# Air_Quality_Sensors.net
KiCad netlist of a schematic drawn in Altium Designer
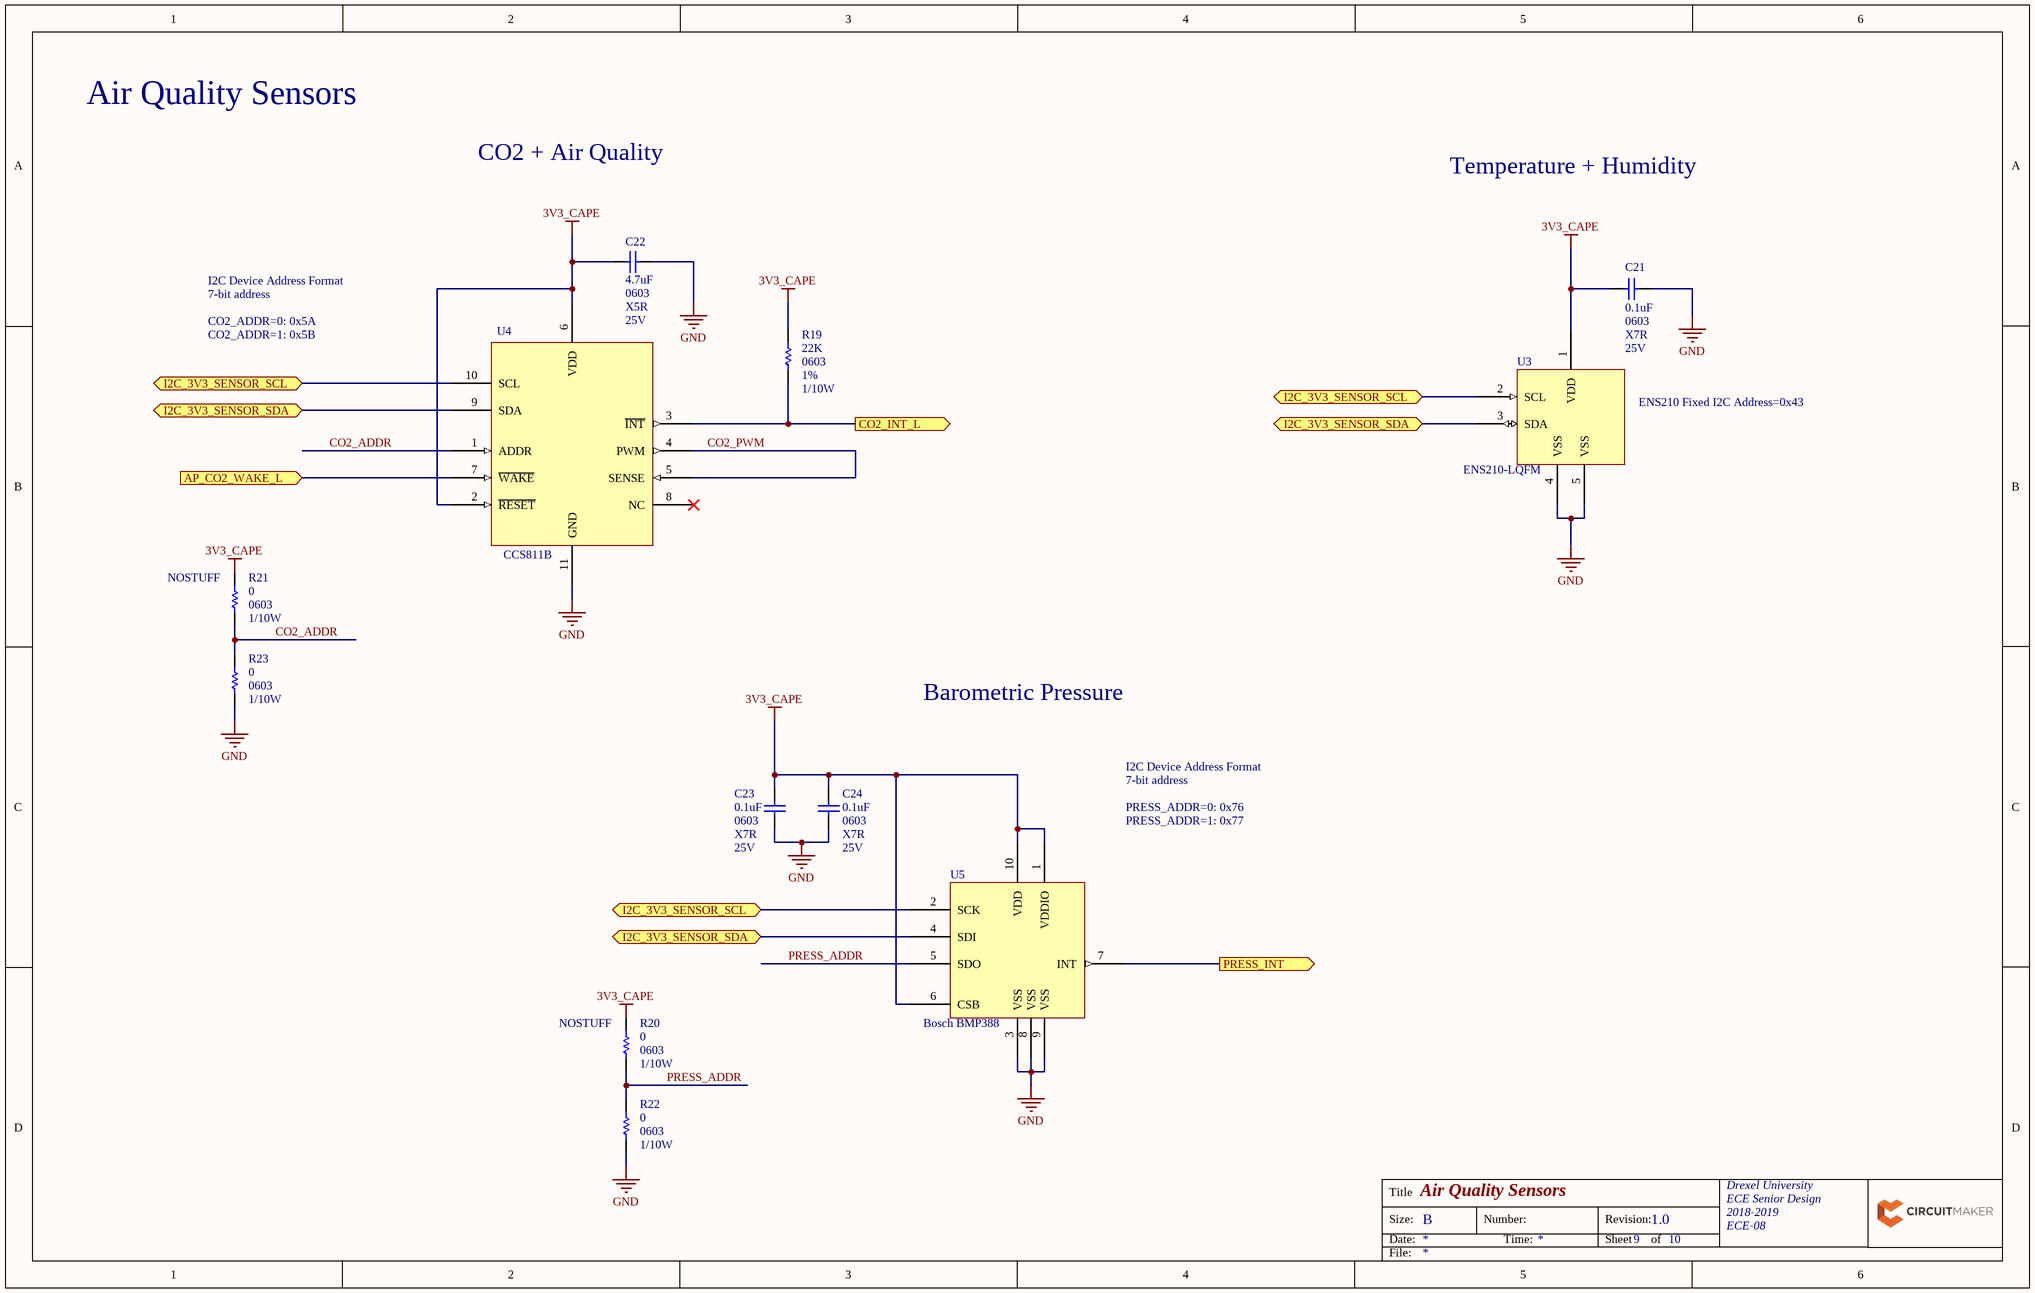
[diagram p0: Air Quality Sensors.SchDoc]

(export (version "E")
  (design (tool "Eeschema 10.0.6"))
  (components
    (comp (ref "C21")
      (value "Würth Elektronik 885012206071")
      (footprint "PCB-8usp83j76ntw2xroyu3n-1")
      (description "Multilayer Ceramic Capacitor, WCAP-CSGP Series, 0.1 F, 10%, X7R, 25 V, 0603 [1608 Metric]")
      (fields
        (field (name "DIELECTRIC CHARACTERISTIC") "X7R")
        (field (name "VOLTAGE RATING (DC)") "25V")
        (field (name "CAPACITANCE") "0.1uF")
        (field (name "MANUFACTURER PART NUMBER") "885012206071")
        (field (name "PACKAGE") "0603")
      )
      (libsource (lib "CommunityVault") (part "CMP-034ac9768ab0dc8d-1"))
    )
    (comp (ref "C22")
      (value "Murata GRM188R61E475KE11D")
      (footprint "CAPC1608X90X35ML10T15")
      (description "CAP CER 4.7UF 25V 10% X5R 0603")
      (fields
        (field (name "CAPACITANCE") "4.7uF")
        (field (name "CASE/PACKAGE") "0603")
        (field (name "DIELECTRIC CHARACTERISTIC") "X5R")
        (field (name "VOLTAGE RATING (DC)") "25V")
        (field (name "MANUFACTURER PART NUMBER") "GRM188R61E475KE11D")
      )
      (libsource (lib "CommunityVault") (part "CMP-8856396-4"))
    )
    (comp (ref "C23")
      (value "Würth Elektronik 885012206071")
      (footprint "PCB-8usp83j76ntw2xroyu3n-1")
      (description "Multilayer Ceramic Capacitor, WCAP-CSGP Series, 0.1 F, 10%, X7R, 25 V, 0603 [1608 Metric]")
      (fields
        (field (name "DIELECTRIC CHARACTERISTIC") "X7R")
        (field (name "VOLTAGE RATING (DC)") "25V")
        (field (name "CAPACITANCE") "0.1uF")
        (field (name "MANUFACTURER PART NUMBER") "885012206071")
        (field (name "PACKAGE") "0603")
      )
      (libsource (lib "CommunityVault") (part "CMP-034ac9768ab0dc8d-1"))
    )
    (comp (ref "C24")
      (value "Würth Elektronik 885012206071")
      (footprint "PCB-8usp83j76ntw2xroyu3n-1")
      (description "Multilayer Ceramic Capacitor, WCAP-CSGP Series, 0.1 F, 10%, X7R, 25 V, 0603 [1608 Metric]")
      (fields
        (field (name "DIELECTRIC CHARACTERISTIC") "X7R")
        (field (name "VOLTAGE RATING (DC)") "25V")
        (field (name "CAPACITANCE") "0.1uF")
        (field (name "MANUFACTURER PART NUMBER") "885012206071")
        (field (name "PACKAGE") "0603")
      )
      (libsource (lib "CommunityVault") (part "CMP-034ac9768ab0dc8d-1"))
    )
    (comp (ref "R19")
      (value "Yageo RC0603FR-0722KL")
      (footprint "RESC1608X55X25LL10T15")
      (description "Chip Resistor, 22 KOhm, +/- 1%, 0.1 W, -55 to 155 degC, 0603 (1608 Metric), RoHS, Tape and Reel")
      (fields
        (field (name "RESISTANCE") "22K")
        (field (name "RESISTANCE TOLERANCE") "1%")
        (field (name "CASE/PACKAGE") "0603")
        (field (name "POWER RATING") "1/10W")
        (field (name "MANUFACTURER PART NUMBER") "RC0603FR-0722KL")
      )
      (libsource (lib "CommunityVault") (part "CMP-1853446-5"))
    )
    (comp (ref "R20")
      (value "Res1")
      (footprint "PCB-vghjuybc2rzv8513tm8h-1")
      (description "RES SMD 0 OHM JUMPER 1/10W 0603")
      (fields
        (field (name "SUPPLIER DEVICE PACKAGE") "0603")
        (field (name "MANUFACTURER PART NUMBER") "RC0603JR-070RL")
        (field (name "RESISTANCE") "0")
        (field (name "POWER") "1/10W")
        (field (name "ALTIUM_UNNAMED_1") "NOSTUFF")
      )
      (libsource (lib "CommunityVault") (part "CMP-536b9a7387ce8cac-9"))
    )
    (comp (ref "R21")
      (value "Res1")
      (footprint "PCB-vghjuybc2rzv8513tm8h-1")
      (description "RES SMD 0 OHM JUMPER 1/10W 0603")
      (fields
        (field (name "SUPPLIER DEVICE PACKAGE") "0603")
        (field (name "MANUFACTURER PART NUMBER") "RC0603JR-070RL")
        (field (name "RESISTANCE") "0")
        (field (name "POWER") "1/10W")
        (field (name "ALTIUM_UNNAMED_1") "NOSTUFF")
      )
      (libsource (lib "CommunityVault") (part "CMP-536b9a7387ce8cac-9"))
    )
    (comp (ref "R22")
      (value "Res1")
      (footprint "PCB-vghjuybc2rzv8513tm8h-1")
      (description "RES SMD 0 OHM JUMPER 1/10W 0603")
      (fields
        (field (name "SUPPLIER DEVICE PACKAGE") "0603")
        (field (name "MANUFACTURER PART NUMBER") "RC0603JR-070RL")
        (field (name "RESISTANCE") "0")
        (field (name "POWER") "1/10W")
      )
      (libsource (lib "CommunityVault") (part "CMP-536b9a7387ce8cac-9"))
    )
    (comp (ref "R23")
      (value "Res1")
      (footprint "PCB-vghjuybc2rzv8513tm8h-1")
      (description "RES SMD 0 OHM JUMPER 1/10W 0603")
      (fields
        (field (name "SUPPLIER DEVICE PACKAGE") "0603")
        (field (name "MANUFACTURER PART NUMBER") "RC0603JR-070RL")
        (field (name "RESISTANCE") "0")
        (field (name "POWER") "1/10W")
      )
      (libsource (lib "CommunityVault") (part "CMP-536b9a7387ce8cac-9"))
    )
    (comp (ref "U3")
      (value "ENS210-LQFM")
      (footprint "DFN95P200X80-4N")
      (description "Humidity/Temperature Sensor Digital Serial (2-Wire, I2C) 4-Pin QFN EP T/R")
      (libsource (lib "CommunityVault") (part "CMP-d38f1e156f1a0c48-1"))
    )
    (comp (ref "U4")
      (value "CCS811B")
      (footprint "CCS811B")
      (description "Low Power Digital Sensor For Ind")
      (fields (field (name "MANUFACTURER PART NUMBER") "CCS811B-JOPD500"))
      (libsource (lib "CommunityVault") (part "CMP-1175dd4b038fceb2-3"))
    )
    (comp (ref "U5")
      (value "Bosch BMP388")
      (footprint "BMP388")
      (description "Pressure Sensor by Bosch Sensortec")
      (fields (field (name "MANUFACTURER PART NUMBER") "BMP388"))
      (libsource (lib "CommunityVault") (part "CMP-7accb6959f30a50b-7"))
    )
  )
  (nets
    (net (code "1") (name "/AP_CO2_WAKE_L") (class "Default")
      (node (ref "U4") (pin "7") (pinfunction "~{WAKE}_7") (pintype "input"))
    )
    (net (code "2") (name "/CO2_ADDR") (class "Default")
      (node (ref "R21") (pin "1") (pinfunction "1_1") (pintype "passive"))
      (node (ref "R23") (pin "2") (pinfunction "2_2") (pintype "passive"))
      (node (ref "U4") (pin "1") (pinfunction "ADDR_1") (pintype "input"))
    )
    (net (code "3") (name "/CO2_INT_L") (class "Default")
      (node (ref "R19") (pin "1") (pinfunction "1_1") (pintype "passive"))
      (node (ref "U4") (pin "3") (pinfunction "~{INT}_3") (pintype "output"))
    )
    (net (code "4") (name "/CO2_PWM") (class "Default")
      (node (ref "U4") (pin "4") (pinfunction "PWM_4") (pintype "output"))
      (node (ref "U4") (pin "5") (pinfunction "SENSE_5") (pintype "input"))
    )
    (net (code "5") (name "/I2C_3V3_SENSOR_SCL") (class "Default")
      (node (ref "U3") (pin "2") (pinfunction "SCL_2") (pintype "input"))
      (node (ref "U4") (pin "10") (pinfunction "SCL_10") (pintype "open_collector"))
      (node (ref "U5") (pin "2") (pinfunction "SCK_2") (pintype "passive"))
    )
    (net (code "6") (name "/I2C_3V3_SENSOR_SDA") (class "Default")
      (node (ref "U3") (pin "3") (pinfunction "SDA_3") (pintype "bidirectional"))
      (node (ref "U4") (pin "9") (pinfunction "SDA_9") (pintype "open_collector"))
      (node (ref "U5") (pin "4") (pinfunction "SDI_4") (pintype "passive"))
    )
    (net (code "7") (name "/PRESS_ADDR") (class "Default")
      (node (ref "R20") (pin "1") (pinfunction "1_1") (pintype "passive"))
      (node (ref "R22") (pin "2") (pinfunction "2_2") (pintype "passive"))
      (node (ref "U5") (pin "5") (pinfunction "SDO_5") (pintype "passive"))
    )
    (net (code "8") (name "/PRESS_INT") (class "Default")
      (node (ref "U5") (pin "7") (pinfunction "INT_7") (pintype "output"))
    )
    (net (code "9") (name "3V3_CAPE") (class "Default")
      (node (ref "C21") (pin "1") (pinfunction "1_1") (pintype "passive"))
      (node (ref "C22") (pin "2") (pinfunction "2_2") (pintype "passive"))
      (node (ref "C23") (pin "2") (pinfunction "2_2") (pintype "passive"))
      (node (ref "C24") (pin "2") (pinfunction "2_2") (pintype "passive"))
      (node (ref "R19") (pin "2") (pinfunction "2_2") (pintype "passive"))
      (node (ref "R20") (pin "2") (pinfunction "2_2") (pintype "passive"))
      (node (ref "R21") (pin "2") (pinfunction "2_2") (pintype "passive"))
      (node (ref "U3") (pin "1") (pinfunction "VDD_1") (pintype "power_in"))
      (node (ref "U4") (pin "2") (pinfunction "~{RESET}_2") (pintype "input"))
      (node (ref "U4") (pin "6") (pinfunction "VDD_6") (pintype "power_in"))
      (node (ref "U5") (pin "1") (pinfunction "VDDIO_1") (pintype "power_in"))
      (node (ref "U5") (pin "10") (pinfunction "VDD_10") (pintype "power_in"))
      (node (ref "U5") (pin "6") (pinfunction "CSB_6") (pintype "passive"))
    )
    (net (code "10") (name "GND") (class "Default")
      (node (ref "C21") (pin "2") (pinfunction "2_2") (pintype "passive"))
      (node (ref "C22") (pin "1") (pinfunction "1_1") (pintype "passive"))
      (node (ref "C23") (pin "1") (pinfunction "1_1") (pintype "passive"))
      (node (ref "C24") (pin "1") (pinfunction "1_1") (pintype "passive"))
      (node (ref "R22") (pin "1") (pinfunction "1_1") (pintype "passive"))
      (node (ref "R23") (pin "1") (pinfunction "1_1") (pintype "passive"))
      (node (ref "U3") (pin "4") (pinfunction "VSS_4") (pintype "power_in"))
      (node (ref "U3") (pin "5") (pinfunction "VSS_5") (pintype "power_in"))
      (node (ref "U4") (pin "11") (pinfunction "GND_11") (pintype "power_in"))
      (node (ref "U5") (pin "3") (pinfunction "VSS_3") (pintype "power_in"))
      (node (ref "U5") (pin "8") (pinfunction "VSS_8") (pintype "power_in"))
      (node (ref "U5") (pin "9") (pinfunction "VSS_9") (pintype "power_in"))
    )
    (net (code "11") (name "unconnected-(U4-NC-Pad8)") (class "Default")
      (node (ref "U4") (pin "8") (pinfunction "NC_8") (pintype "passive+no_connect"))
    )
  )
)
